# CircuitDiagram.net
KiCad netlist of a schematic drawn in EAGLE
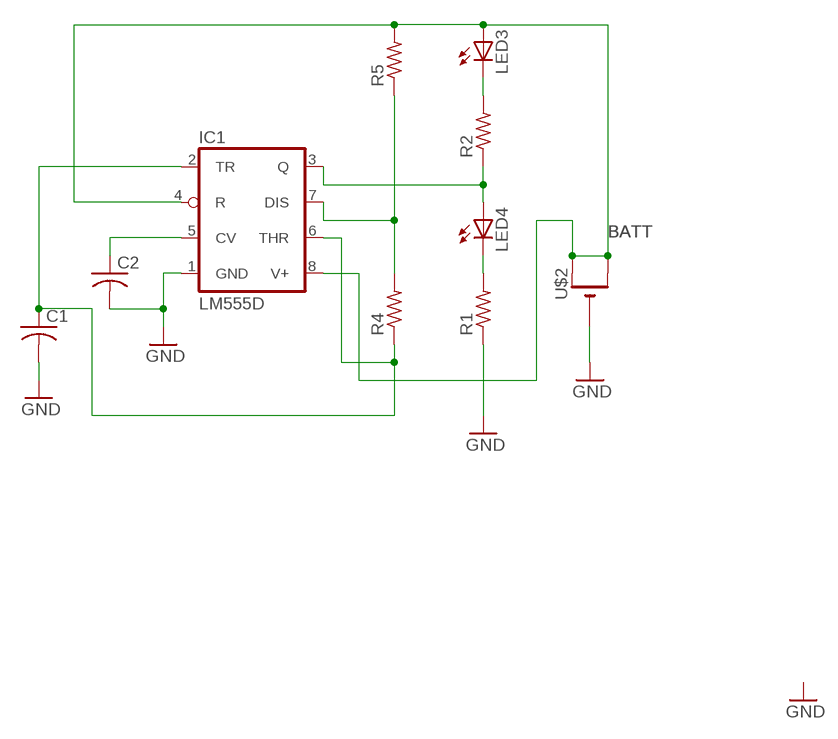
[diagram p0: schematic, sheet 1]

(export (version "E")
  (design (tool "Eeschema 10.0.6"))
  (components
    (comp (ref "C1")
      (value "C-USC0805")
      (footprint "eagle-import:C0805")
      (libsource (lib "eagle-import") (part "C-USC0805"))
    )
    (comp (ref "C2")
      (value "C-USC0805")
      (footprint "eagle-import:C0805")
      (libsource (lib "eagle-import") (part "C-USC0805"))
    )
    (comp (ref "IC1")
      (value "LM555D")
      (footprint "eagle-import:SO08")
      (libsource (lib "eagle-import") (part "555DLM"))
    )
    (comp (ref "LED3")
      (value "LEDCHIP-LED0805")
      (footprint "eagle-import:CHIP-LED0805")
      (libsource (lib "eagle-import") (part "LEDCHIP-LED0805"))
    )
    (comp (ref "LED4")
      (value "LEDCHIP-LED0805")
      (footprint "eagle-import:CHIP-LED0805")
      (libsource (lib "eagle-import") (part "LEDCHIP-LED0805"))
    )
    (comp (ref "R1")
      (value "R-US_R0805")
      (footprint "eagle-import:R0805")
      (libsource (lib "eagle-import") (part "R-US_R0805"))
    )
    (comp (ref "R2")
      (value "R-US_R0805")
      (footprint "eagle-import:R0805")
      (libsource (lib "eagle-import") (part "R-US_R0805"))
    )
    (comp (ref "R4")
      (value "R-US_R0805")
      (footprint "eagle-import:R0805")
      (libsource (lib "eagle-import") (part "R-US_R0805"))
    )
    (comp (ref "R5")
      (value "R-US_R0805")
      (footprint "eagle-import:R0805")
      (libsource (lib "eagle-import") (part "R-US_R0805"))
    )
    (comp (ref "U$2")
      (value "CR1220SMT")
      (footprint "eagle-import:CR1220-SMD")
      (libsource (lib "eagle-import") (part "CR1220SMT"))
    )
  )
  (nets
    (net (code "1") (name "/BATT") (class "Default")
      (node (ref "IC1") (pin "4") (pinfunction "R_4") (pintype "input"))
      (node (ref "IC1") (pin "8") (pinfunction "V+_8") (pintype "power_in"))
      (node (ref "LED3") (pin "A") (pinfunction "A_A") (pintype "passive"))
      (node (ref "R5") (pin "2") (pinfunction "2_2") (pintype "passive"))
      (node (ref "U$2") (pin "+$1") (pinfunction "+_+$1") (pintype "passive"))
      (node (ref "U$2") (pin "+$2") (pinfunction "+1_+$2") (pintype "passive"))
    )
    (net (code "2") (name "GND") (class "Default")
      (node (ref "C1") (pin "2") (pinfunction "2_2") (pintype "passive"))
      (node (ref "C2") (pin "2") (pinfunction "2_2") (pintype "passive"))
      (node (ref "IC1") (pin "1") (pinfunction "GND_1") (pintype "power_in"))
      (node (ref "R1") (pin "1") (pinfunction "1_1") (pintype "passive"))
      (node (ref "U$2") (pin "-") (pinfunction "-_-") (pintype "passive"))
    )
    (net (code "3") (name "Net-(IC1-CV)") (class "Default")
      (node (ref "C2") (pin "1") (pinfunction "1_1") (pintype "passive"))
      (node (ref "IC1") (pin "5") (pinfunction "CV_5") (pintype "input"))
    )
    (net (code "4") (name "Net-(IC1-DIS)") (class "Default")
      (node (ref "IC1") (pin "7") (pinfunction "DIS_7") (pintype "input"))
      (node (ref "R4") (pin "2") (pinfunction "2_2") (pintype "passive"))
      (node (ref "R5") (pin "1") (pinfunction "1_1") (pintype "passive"))
    )
    (net (code "5") (name "Net-(IC1-Q)") (class "Default")
      (node (ref "IC1") (pin "3") (pinfunction "Q_3") (pintype "output"))
      (node (ref "LED4") (pin "A") (pinfunction "A_A") (pintype "passive"))
      (node (ref "R2") (pin "1") (pinfunction "1_1") (pintype "passive"))
    )
    (net (code "6") (name "Net-(IC1-THR)") (class "Default")
      (node (ref "C1") (pin "1") (pinfunction "1_1") (pintype "passive"))
      (node (ref "IC1") (pin "2") (pinfunction "TR_2") (pintype "input"))
      (node (ref "IC1") (pin "6") (pinfunction "THR_6") (pintype "input"))
      (node (ref "R4") (pin "1") (pinfunction "1_1") (pintype "passive"))
    )
    (net (code "7") (name "Net-(LED3-PadC)") (class "Default")
      (node (ref "LED3") (pin "C") (pinfunction "C_C") (pintype "passive"))
      (node (ref "R2") (pin "2") (pinfunction "2_2") (pintype "passive"))
    )
    (net (code "8") (name "Net-(LED4-PadC)") (class "Default")
      (node (ref "LED4") (pin "C") (pinfunction "C_C") (pintype "passive"))
      (node (ref "R1") (pin "2") (pinfunction "2_2") (pintype "passive"))
    )
  )
)
